# schaltplan.net
KiCad netlist of a schematic drawn in EAGLE
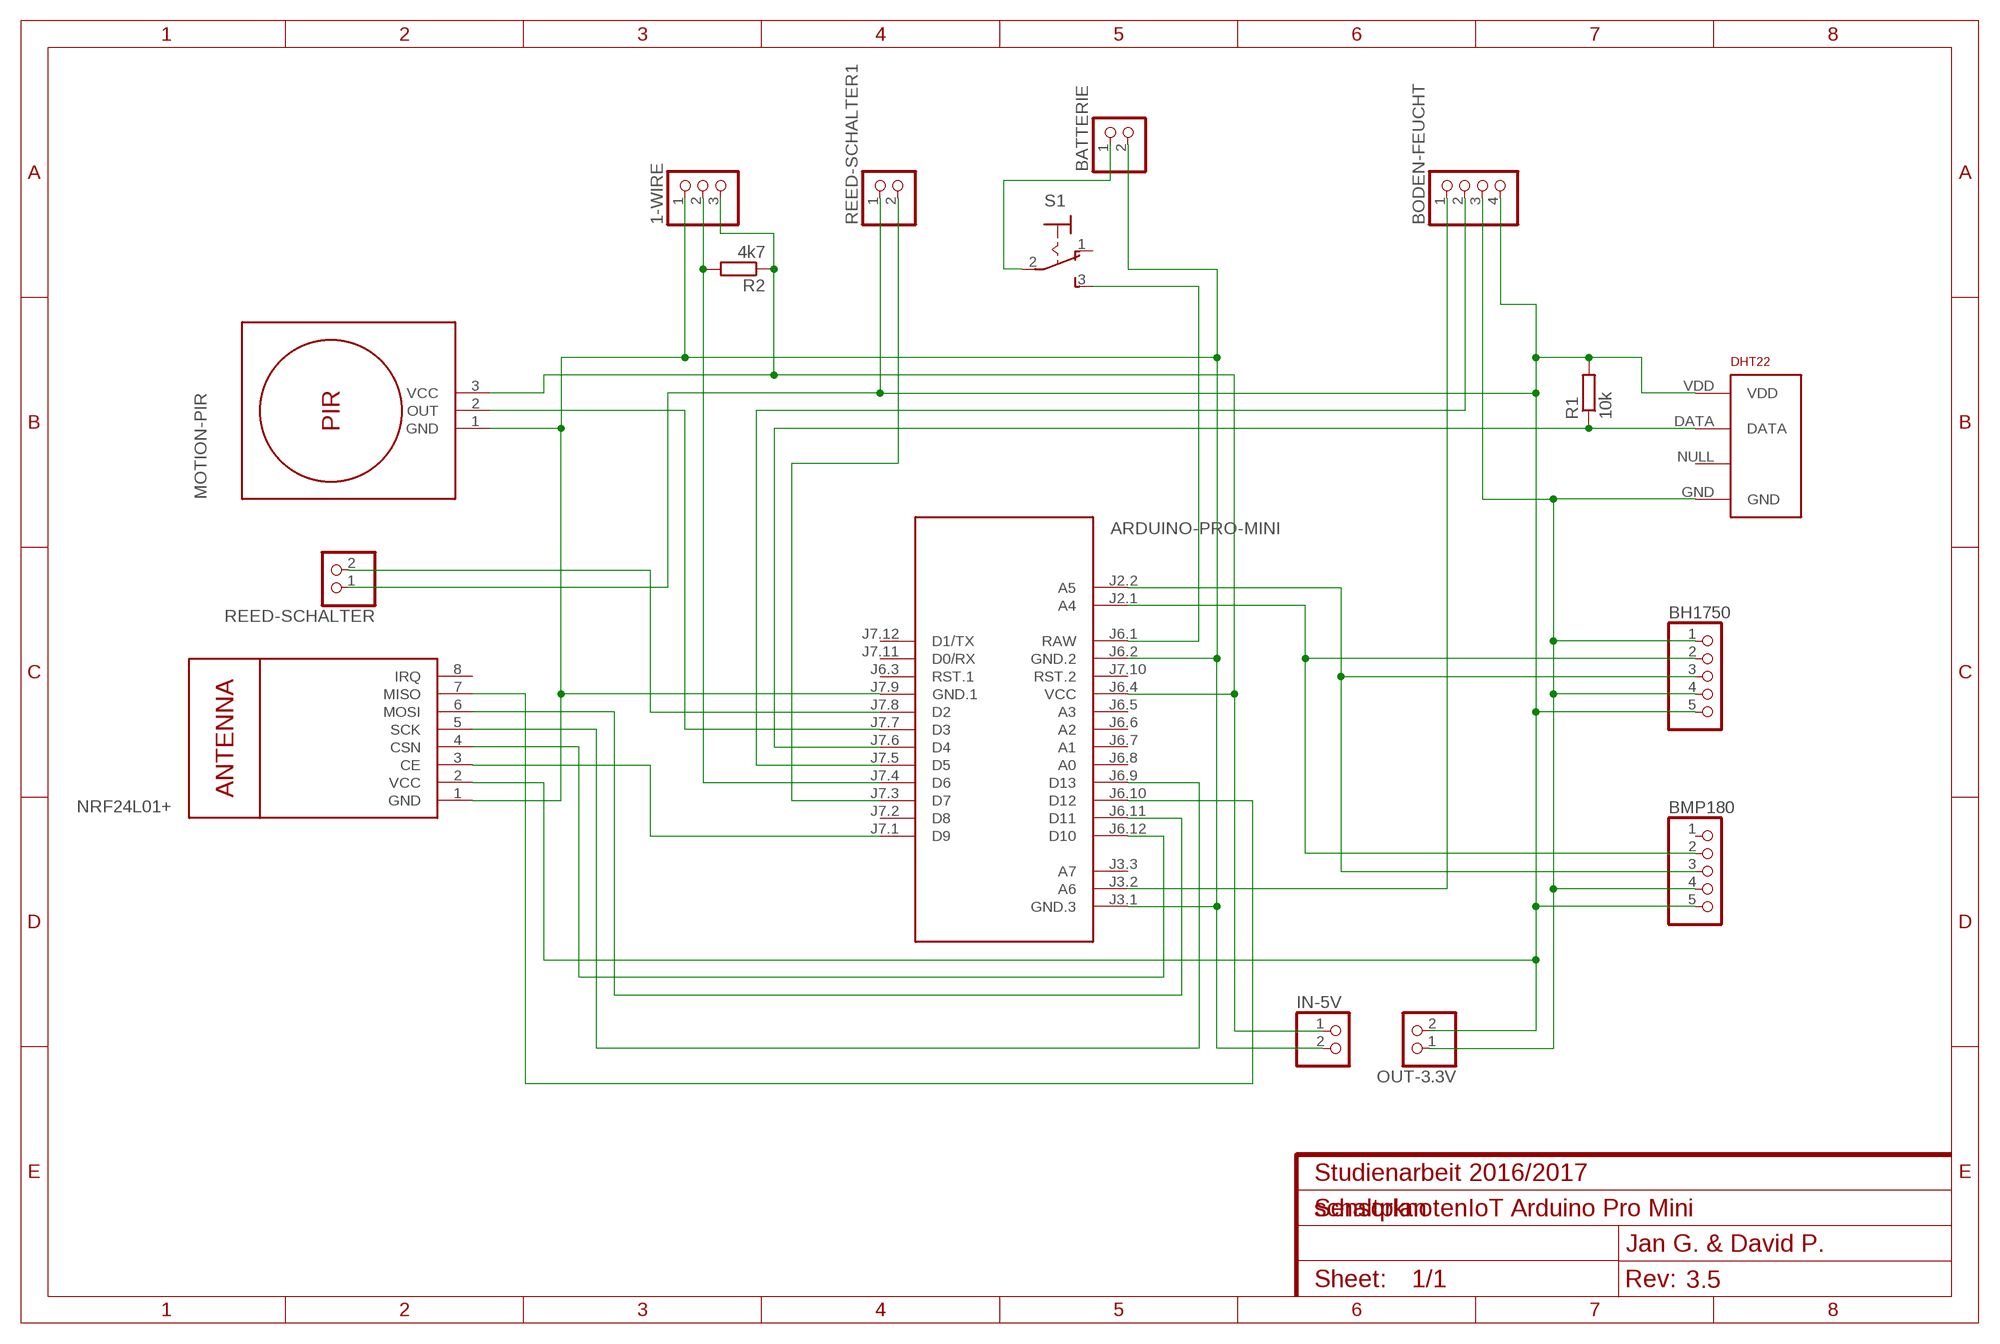
[diagram p0: schematic, sheet 1]

(export (version "E")
  (design (tool "Eeschema 10.0.6"))
  (components
    (comp (ref "1-WIRE")
      (value "PINHD-1X3")
      (footprint "eagle-import:1X03")
      (libsource (lib "eagle-import") (part "PINHD-1X3"))
    )
    (comp (ref "ARDUINO-PRO-MINI")
      (value "ARDUINO-PRO-MINI-5.0V#NP")
      (footprint "eagle-import:ARDUINO-PRO-MINI#NP")
      (libsource (lib "eagle-import") (part "ARDUINO-PRO-MINI-#NP5.0V"))
    )
    (comp (ref "BATTERIE")
      (value "PINHD-1X2")
      (footprint "eagle-import:1X02")
      (libsource (lib "eagle-import") (part "PINHD-1X2"))
    )
    (comp (ref "BH1750")
      (value "PINHD-1X5")
      (footprint "eagle-import:1X05")
      (libsource (lib "eagle-import") (part "PINHD-1X5"))
    )
    (comp (ref "BMP180")
      (value "PINHD-1X5")
      (footprint "eagle-import:1X05")
      (libsource (lib "eagle-import") (part "PINHD-1X5"))
    )
    (comp (ref "BODEN-FEUCHT")
      (value "PINHD-1X4")
      (footprint "eagle-import:1X04")
      (libsource (lib "eagle-import") (part "PINHD-1X4"))
    )
    (comp (ref "DHT22")
      (value "RHT03_DHT-22_AM2302")
      (footprint "eagle-import:RHT03_DHT-22")
      (libsource (lib "eagle-import") (part "RHT03_DHT-22_AM2302"))
    )
    (comp (ref "IN-5V")
      (value "PINHD-1X2")
      (footprint "eagle-import:1X02")
      (libsource (lib "eagle-import") (part "PINHD-1X2"))
    )
    (comp (ref "MOTION-PIR")
      (value "MOTION-PIR-DYP-ME003")
      (footprint "eagle-import:MOTION-PIR-DYP-ME003")
      (libsource (lib "eagle-import") (part "MOTION-PIR-DYP-ME003"))
    )
    (comp (ref "NRF24L01+")
      (value "WIRELESS-NRF24L01")
      (footprint "eagle-import:WIRELESS-NRF24L01")
      (libsource (lib "eagle-import") (part "WIRELESS-NRF24L01"))
    )
    (comp (ref "OUT-3.3V")
      (value "PINHD-1X2")
      (footprint "eagle-import:1X02")
      (libsource (lib "eagle-import") (part "PINHD-1X2"))
    )
    (comp (ref "R1")
      (value "10k")
      (footprint "eagle-import:0207_10")
      (libsource (lib "eagle-import") (part "R-EU_0207/10"))
    )
    (comp (ref "R2")
      (value "4k7")
      (footprint "eagle-import:0207_10")
      (libsource (lib "eagle-import") (part "R-EU_0207/10"))
    )
    (comp (ref "REED-SCHALTER")
      (value "PINHD-1X2")
      (footprint "eagle-import:1X02")
      (libsource (lib "eagle-import") (part "PINHD-1X2"))
    )
    (comp (ref "REED-SCHALTER1")
      (value "PINHD-1X2")
      (footprint "eagle-import:1X02")
      (libsource (lib "eagle-import") (part "PINHD-1X2"))
    )
    (comp (ref "S1")
      (value "320-916")
      (footprint "eagle-import:320-916")
      (libsource (lib "eagle-import") (part "320-916"))
    )
  )
  (nets
    (net (code "1") (name "/GND") (class "Default")
      (node (ref "1-WIRE") (pin "1") (pinfunction "1_1") (pintype "passive"))
      (node (ref "ARDUINO-PRO-MINI") (pin "J3.1") (pinfunction "GND.3_J3.1") (pintype "bidirectional"))
      (node (ref "ARDUINO-PRO-MINI") (pin "J6.2") (pinfunction "GND.2_J6.2") (pintype "power_in"))
      (node (ref "ARDUINO-PRO-MINI") (pin "J7.9") (pinfunction "GND.1_J7.9") (pintype "power_in"))
      (node (ref "BATTERIE") (pin "2") (pinfunction "2_2") (pintype "passive"))
      (node (ref "BH1750") (pin "1") (pinfunction "1_1") (pintype "passive"))
      (node (ref "BH1750") (pin "4") (pinfunction "4_4") (pintype "passive"))
      (node (ref "BMP180") (pin "4") (pinfunction "4_4") (pintype "passive"))
      (node (ref "BODEN-FEUCHT") (pin "3") (pinfunction "3_3") (pintype "passive"))
      (node (ref "DHT22") (pin "GND") (pinfunction "GND_GND") (pintype "power_in"))
      (node (ref "IN-5V") (pin "2") (pinfunction "2_2") (pintype "passive"))
      (node (ref "MOTION-PIR") (pin "1") (pinfunction "GND_1") (pintype "power_in"))
      (node (ref "NRF24L01+") (pin "1") (pinfunction "GND_1") (pintype "power_in"))
      (node (ref "OUT-3.3V") (pin "1") (pinfunction "1_1") (pintype "passive"))
    )
    (net (code "2") (name "Net-(ARDUINO-PRO-MINI-A4)") (class "Default")
      (node (ref "ARDUINO-PRO-MINI") (pin "J2.1") (pinfunction "A4_J2.1") (pintype "bidirectional"))
      (node (ref "BH1750") (pin "2") (pinfunction "2_2") (pintype "passive"))
      (node (ref "BMP180") (pin "2") (pinfunction "2_2") (pintype "passive"))
    )
    (net (code "3") (name "Net-(ARDUINO-PRO-MINI-A5)") (class "Default")
      (node (ref "ARDUINO-PRO-MINI") (pin "J2.2") (pinfunction "A5_J2.2") (pintype "bidirectional"))
      (node (ref "BH1750") (pin "3") (pinfunction "3_3") (pintype "passive"))
      (node (ref "BMP180") (pin "3") (pinfunction "3_3") (pintype "passive"))
    )
    (net (code "4") (name "Net-(ARDUINO-PRO-MINI-A6)") (class "Default")
      (node (ref "ARDUINO-PRO-MINI") (pin "J3.2") (pinfunction "A6_J3.2") (pintype "bidirectional"))
      (node (ref "BODEN-FEUCHT") (pin "1") (pinfunction "1_1") (pintype "passive"))
    )
    (net (code "5") (name "Net-(ARDUINO-PRO-MINI-D2)") (class "Default")
      (node (ref "ARDUINO-PRO-MINI") (pin "J7.8") (pinfunction "D2_J7.8") (pintype "bidirectional"))
      (node (ref "REED-SCHALTER") (pin "2") (pinfunction "2_2") (pintype "passive"))
    )
    (net (code "6") (name "Net-(ARDUINO-PRO-MINI-D3)") (class "Default")
      (node (ref "ARDUINO-PRO-MINI") (pin "J7.7") (pinfunction "D3_J7.7") (pintype "bidirectional"))
      (node (ref "MOTION-PIR") (pin "2") (pinfunction "OUT_2") (pintype "output"))
    )
    (net (code "7") (name "Net-(ARDUINO-PRO-MINI-D4)") (class "Default")
      (node (ref "ARDUINO-PRO-MINI") (pin "J7.6") (pinfunction "D4_J7.6") (pintype "bidirectional"))
      (node (ref "DHT22") (pin "DATA") (pinfunction "DATA_DATA") (pintype "bidirectional"))
      (node (ref "R1") (pin "1") (pinfunction "1_1") (pintype "passive"))
    )
    (net (code "8") (name "Net-(ARDUINO-PRO-MINI-D5)") (class "Default")
      (node (ref "ARDUINO-PRO-MINI") (pin "J7.5") (pinfunction "D5_J7.5") (pintype "bidirectional"))
      (node (ref "BODEN-FEUCHT") (pin "2") (pinfunction "2_2") (pintype "passive"))
    )
    (net (code "9") (name "Net-(ARDUINO-PRO-MINI-D6)") (class "Default")
      (node (ref "1-WIRE") (pin "2") (pinfunction "2_2") (pintype "passive"))
      (node (ref "ARDUINO-PRO-MINI") (pin "J7.4") (pinfunction "D6_J7.4") (pintype "bidirectional"))
      (node (ref "R2") (pin "2") (pinfunction "2_2") (pintype "passive"))
    )
    (net (code "10") (name "Net-(ARDUINO-PRO-MINI-D7)") (class "Default")
      (node (ref "ARDUINO-PRO-MINI") (pin "J7.3") (pinfunction "D7_J7.3") (pintype "bidirectional"))
      (node (ref "REED-SCHALTER1") (pin "2") (pinfunction "2_2") (pintype "passive"))
    )
    (net (code "11") (name "Net-(ARDUINO-PRO-MINI-D9)") (class "Default")
      (node (ref "ARDUINO-PRO-MINI") (pin "J7.1") (pinfunction "D9_J7.1") (pintype "bidirectional"))
      (node (ref "NRF24L01+") (pin "3") (pinfunction "CE_3") (pintype "bidirectional"))
    )
    (net (code "12") (name "Net-(ARDUINO-PRO-MINI-D10)") (class "Default")
      (node (ref "ARDUINO-PRO-MINI") (pin "J6.12") (pinfunction "D10_J6.12") (pintype "bidirectional"))
      (node (ref "NRF24L01+") (pin "4") (pinfunction "CSN_4") (pintype "bidirectional"))
    )
    (net (code "13") (name "Net-(ARDUINO-PRO-MINI-D11)") (class "Default")
      (node (ref "ARDUINO-PRO-MINI") (pin "J6.11") (pinfunction "D11_J6.11") (pintype "bidirectional"))
      (node (ref "NRF24L01+") (pin "6") (pinfunction "MOSI_6") (pintype "bidirectional"))
    )
    (net (code "14") (name "Net-(ARDUINO-PRO-MINI-D12)") (class "Default")
      (node (ref "ARDUINO-PRO-MINI") (pin "J6.10") (pinfunction "D12_J6.10") (pintype "bidirectional"))
      (node (ref "NRF24L01+") (pin "7") (pinfunction "MISO_7") (pintype "bidirectional"))
    )
    (net (code "15") (name "Net-(ARDUINO-PRO-MINI-D13)") (class "Default")
      (node (ref "ARDUINO-PRO-MINI") (pin "J6.9") (pinfunction "D13_J6.9") (pintype "bidirectional"))
      (node (ref "NRF24L01+") (pin "5") (pinfunction "SCK_5") (pintype "bidirectional"))
    )
    (net (code "16") (name "Net-(ARDUINO-PRO-MINI-RAW)") (class "Default")
      (node (ref "ARDUINO-PRO-MINI") (pin "J6.1") (pinfunction "RAW_J6.1") (pintype "power_in"))
      (node (ref "S1") (pin "3") (pinfunction "S_3") (pintype "passive"))
    )
    (net (code "17") (name "Net-(ARDUINO-PRO-MINI-VCC)") (class "Default")
      (node (ref "1-WIRE") (pin "3") (pinfunction "3_3") (pintype "passive"))
      (node (ref "ARDUINO-PRO-MINI") (pin "J6.4") (pinfunction "VCC_J6.4") (pintype "power_in"))
      (node (ref "IN-5V") (pin "1") (pinfunction "1_1") (pintype "passive"))
      (node (ref "MOTION-PIR") (pin "3") (pinfunction "VCC_3") (pintype "power_in"))
      (node (ref "R2") (pin "1") (pinfunction "1_1") (pintype "passive"))
    )
    (net (code "18") (name "Net-(NRF24L01+-VCC)") (class "Default")
      (node (ref "BH1750") (pin "5") (pinfunction "5_5") (pintype "passive"))
      (node (ref "BMP180") (pin "5") (pinfunction "5_5") (pintype "passive"))
      (node (ref "BODEN-FEUCHT") (pin "4") (pinfunction "4_4") (pintype "passive"))
      (node (ref "DHT22") (pin "VDD") (pinfunction "VDD_VDD") (pintype "power_in"))
      (node (ref "NRF24L01+") (pin "2") (pinfunction "VCC_2") (pintype "power_in"))
      (node (ref "OUT-3.3V") (pin "2") (pinfunction "2_2") (pintype "passive"))
      (node (ref "R1") (pin "2") (pinfunction "2_2") (pintype "passive"))
      (node (ref "REED-SCHALTER") (pin "1") (pinfunction "1_1") (pintype "passive"))
      (node (ref "REED-SCHALTER1") (pin "1") (pinfunction "1_1") (pintype "passive"))
    )
    (net (code "19") (name "Net-(S1-P)") (class "Default")
      (node (ref "BATTERIE") (pin "1") (pinfunction "1_1") (pintype "passive"))
      (node (ref "S1") (pin "2") (pinfunction "P_2") (pintype "passive"))
    )
    (net (code "20") (name "unconnected-(ARDUINO-PRO-MINI-A0-PadJ6.8)") (class "Default")
      (node (ref "ARDUINO-PRO-MINI") (pin "J6.8") (pinfunction "A0_J6.8") (pintype "bidirectional"))
    )
    (net (code "21") (name "unconnected-(ARDUINO-PRO-MINI-A1-PadJ6.7)") (class "Default")
      (node (ref "ARDUINO-PRO-MINI") (pin "J6.7") (pinfunction "A1_J6.7") (pintype "bidirectional"))
    )
    (net (code "22") (name "unconnected-(ARDUINO-PRO-MINI-A2-PadJ6.6)") (class "Default")
      (node (ref "ARDUINO-PRO-MINI") (pin "J6.6") (pinfunction "A2_J6.6") (pintype "bidirectional"))
    )
    (net (code "23") (name "unconnected-(ARDUINO-PRO-MINI-A3-PadJ6.5)") (class "Default")
      (node (ref "ARDUINO-PRO-MINI") (pin "J6.5") (pinfunction "A3_J6.5") (pintype "bidirectional"))
    )
    (net (code "24") (name "unconnected-(ARDUINO-PRO-MINI-A7-PadJ3.3)") (class "Default")
      (node (ref "ARDUINO-PRO-MINI") (pin "J3.3") (pinfunction "A7_J3.3") (pintype "bidirectional"))
    )
    (net (code "25") (name "unconnected-(ARDUINO-PRO-MINI-D0{slash}RX-PadJ7.11)") (class "Default")
      (node (ref "ARDUINO-PRO-MINI") (pin "J7.11") (pinfunction "D0/RX_J7.11") (pintype "bidirectional"))
    )
    (net (code "26") (name "unconnected-(ARDUINO-PRO-MINI-D1{slash}TX-PadJ7.12)") (class "Default")
      (node (ref "ARDUINO-PRO-MINI") (pin "J7.12") (pinfunction "D1/TX_J7.12") (pintype "bidirectional"))
    )
    (net (code "27") (name "unconnected-(ARDUINO-PRO-MINI-D8-PadJ7.2)") (class "Default")
      (node (ref "ARDUINO-PRO-MINI") (pin "J7.2") (pinfunction "D8_J7.2") (pintype "bidirectional"))
    )
    (net (code "28") (name "unconnected-(ARDUINO-PRO-MINI-RST.1-PadJ6.3)") (class "Default")
      (node (ref "ARDUINO-PRO-MINI") (pin "J6.3") (pinfunction "RST.1_J6.3") (pintype "bidirectional"))
    )
    (net (code "29") (name "unconnected-(ARDUINO-PRO-MINI-RST.2-PadJ7.10)") (class "Default")
      (node (ref "ARDUINO-PRO-MINI") (pin "J7.10") (pinfunction "RST.2_J7.10") (pintype "bidirectional"))
    )
    (net (code "30") (name "unconnected-(BMP180-Pad1)") (class "Default")
      (node (ref "BMP180") (pin "1") (pinfunction "1_1") (pintype "passive"))
    )
    (net (code "31") (name "unconnected-(DHT22-PadNULL)") (class "Default")
      (node (ref "DHT22") (pin "NULL") (pinfunction "NULL_NULL") (pintype "no_connect"))
    )
    (net (code "32") (name "unconnected-(NRF24L01+-IRQ-Pad8)") (class "Default")
      (node (ref "NRF24L01+") (pin "8") (pinfunction "IRQ_8") (pintype "bidirectional"))
    )
    (net (code "33") (name "unconnected-(S1-O-Pad1)") (class "Default")
      (node (ref "S1") (pin "1") (pinfunction "O_1") (pintype "passive"))
    )
  )
)
